# Peltier_activation_board.net
KiCad netlist of a schematic drawn in Altium Designer
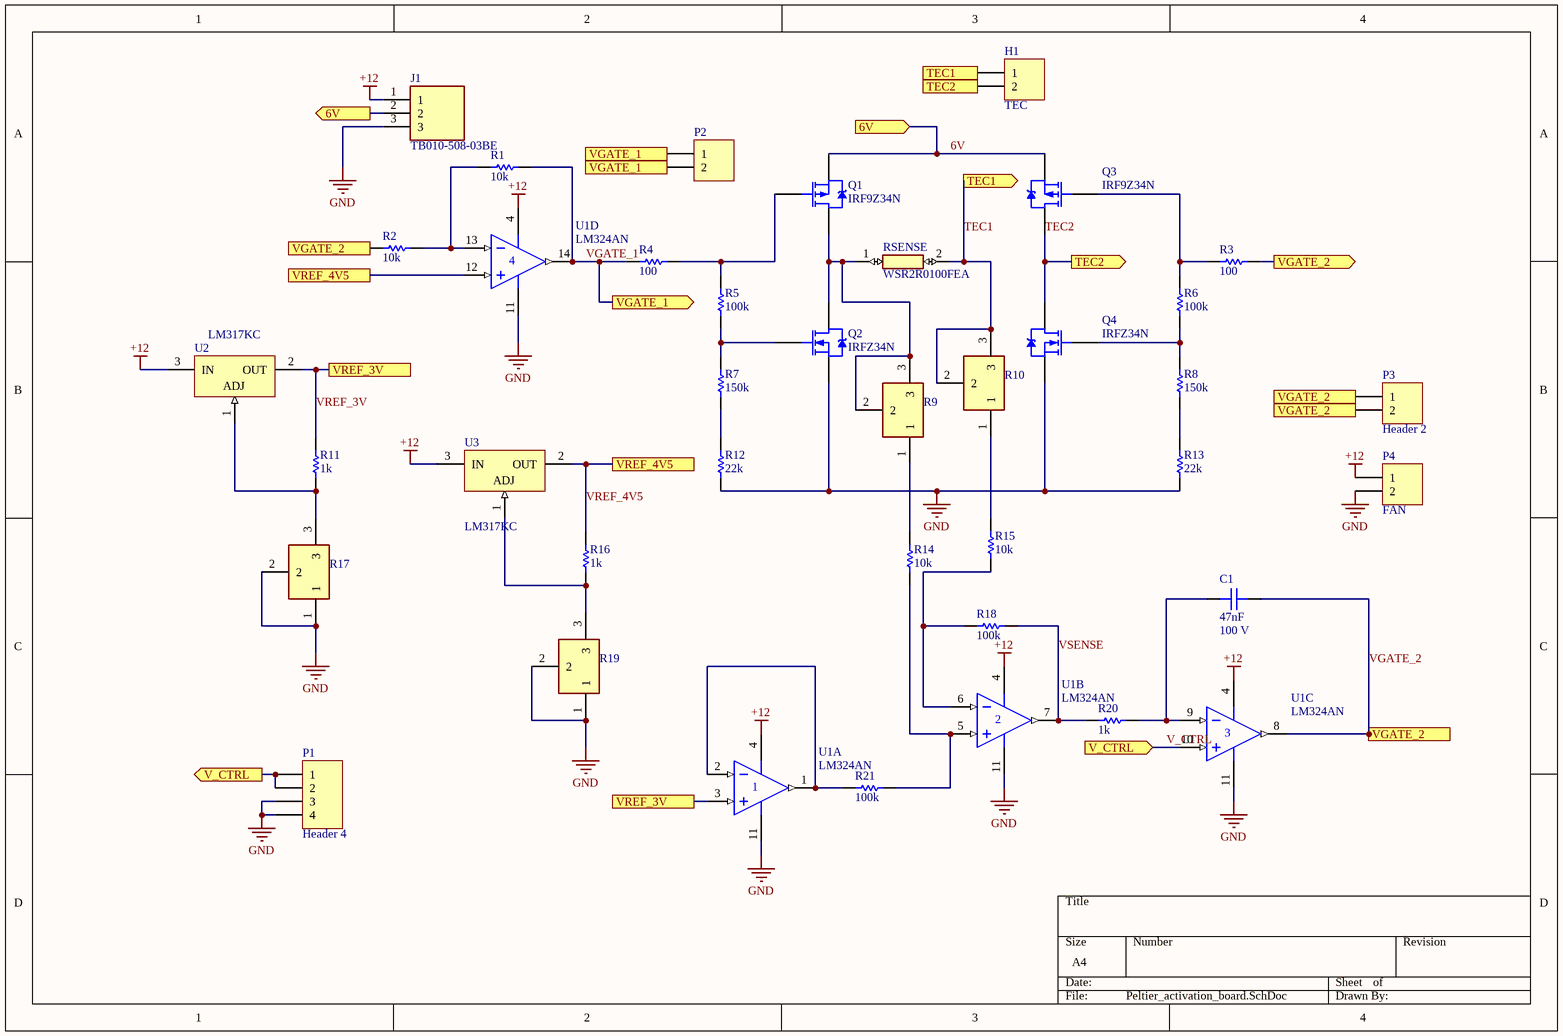
[diagram p0: Peltier_activation_board.SchDoc]

(export (version "E")
  (design (tool "Eeschema 10.0.6"))
  (components
    (comp (ref "C1")
      (value "47nF")
      (footprint "C100-200-100")
      (description "Capacitor")
      (fields (field (name "VOLTAGE") "100 V") (field (name "PUBLISHER") "Altium Limited"))
      (libsource (lib "Amplificador") (part "Capacitor"))
    )
    (comp (ref "H1")
      (value "TEC")
      (footprint "TB02")
      (description "Bloco terminal 1x2")
      (libsource (lib "Amplificador") (part "Terminal_1x2"))
    )
    (comp (ref "J1")
      (value "TB010-508-03BE")
      (footprint "SamacSys:TB01050803BE")
      (description "Connector")
      (fields (field (name "MOUSER PART NUMBER") "490-TB010-508-03BE"))
      (libsource (lib "*") (part "TB010-508-03BE"))
    )
    (comp (ref "P1")
      (value "Header 4")
      (footprint "HDR1X4")
      (description "Header, 4-Pin")
      (fields (field (name "PUBLISHER") "Altium Limited"))
      (libsource (lib "Miscellaneous Connectors") (part "Header 4"))
    )
    (comp (ref "P2")
      (value "~")
      (footprint "HDR1X2")
      (description "Header, 2-Pin")
      (fields (field (name "PUBLISHER") "Altium Limited"))
      (libsource (lib "Miscellaneous Connectors") (part "Header 2"))
    )
    (comp (ref "P3")
      (value "Header 2")
      (footprint "HDR1X2")
      (description "Header, 2-Pin")
      (fields (field (name "PUBLISHER") "Altium Limited"))
      (libsource (lib "Miscellaneous Connectors") (part "Header 2"))
    )
    (comp (ref "P4")
      (value "FAN")
      (footprint "HDR1X2")
      (description "Header, 2-Pin")
      (fields (field (name "PUBLISHER") "Altium Limited"))
      (libsource (lib "Miscellaneous Connectors") (part "Header 2"))
    )
    (comp (ref "Q1")
      (value "IRF9Z34N")
      (footprint "TO-220AB")
      (description "HEXFET Power MOSFET")
      (fields (field (name "PUBLISHER") "Altium Limited"))
      (libsource (lib "IR Discrete MOSFET - Power") (part "IRF9Z34N"))
    )
    (comp (ref "Q2")
      (value "IRFZ34N")
      (footprint "TO-220AB")
      (description "HEXFET Power MOSFET")
      (fields (field (name "PUBLISHER") "Altium Limited"))
      (libsource (lib "IR Discrete MOSFET - Power") (part "IRFZ34N"))
    )
    (comp (ref "Q3")
      (value "IRF9Z34N")
      (footprint "TO-220AB")
      (description "HEXFET Power MOSFET")
      (fields (field (name "PUBLISHER") "Altium Limited"))
      (libsource (lib "IR Discrete MOSFET - Power") (part "IRF9Z34N"))
    )
    (comp (ref "Q4")
      (value "IRFZ34N")
      (footprint "TO-220AB")
      (description "HEXFET Power MOSFET")
      (fields (field (name "PUBLISHER") "Altium Limited"))
      (libsource (lib "IR Discrete MOSFET - Power") (part "IRFZ34N"))
    )
    (comp (ref "R1")
      (value "10k")
      (footprint "R400-2.0mm")
      (description "Resistor")
      (fields
        (field (name "POWER") "1/8 W")
        (field (name "TOLERANCE") "5%")
        (field (name "PUBLISHER") "Altium Limited")
      )
      (libsource (lib "Amplificador") (part "Resistor"))
    )
    (comp (ref "R2")
      (value "10k")
      (footprint "R400-2.0mm")
      (description "Resistor")
      (fields
        (field (name "POWER") "1/8 W")
        (field (name "TOLERANCE") "5%")
        (field (name "PUBLISHER") "Altium Limited")
      )
      (libsource (lib "Amplificador") (part "Resistor"))
    )
    (comp (ref "R3")
      (value "100")
      (footprint "R400-2.0mm")
      (description "Resistor")
      (fields
        (field (name "POWER") "1/8 W")
        (field (name "TOLERANCE") "5%")
        (field (name "PUBLISHER") "Altium Limited")
      )
      (libsource (lib "Amplificador") (part "Resistor"))
    )
    (comp (ref "R4")
      (value "100")
      (footprint "R400-2.0mm")
      (description "Resistor")
      (fields
        (field (name "POWER") "1/8 W")
        (field (name "TOLERANCE") "5%")
        (field (name "PUBLISHER") "Altium Limited")
      )
      (libsource (lib "Amplificador") (part "Resistor"))
    )
    (comp (ref "R5")
      (value "100k")
      (footprint "R400-2.0mm")
      (description "Resistor")
      (fields
        (field (name "POWER") "1/8 W")
        (field (name "TOLERANCE") "5%")
        (field (name "PUBLISHER") "Altium Limited")
      )
      (libsource (lib "Amplificador") (part "Resistor"))
    )
    (comp (ref "R6")
      (value "100k")
      (footprint "R400-2.0mm")
      (description "Resistor")
      (fields
        (field (name "POWER") "1/8 W")
        (field (name "TOLERANCE") "5%")
        (field (name "PUBLISHER") "Altium Limited")
      )
      (libsource (lib "Amplificador") (part "Resistor"))
    )
    (comp (ref "R7")
      (value "150k")
      (footprint "R400-2.0mm")
      (description "Resistor")
      (fields
        (field (name "POWER") "1/8 W")
        (field (name "TOLERANCE") "5%")
        (field (name "PUBLISHER") "Altium Limited")
      )
      (libsource (lib "Amplificador") (part "Resistor"))
    )
    (comp (ref "R8")
      (value "150k")
      (footprint "R400-2.0mm")
      (description "Resistor")
      (fields
        (field (name "POWER") "1/8 W")
        (field (name "TOLERANCE") "5%")
        (field (name "PUBLISHER") "Altium Limited")
      )
      (libsource (lib "Amplificador") (part "Resistor"))
    )
    (comp (ref "R9")
      (value "3006P-1-103LF")
      (footprint "SamacSys:3006P_1")
      (description "Resistor")
      (fields (field (name "MOUSER PART NUMBER") "652-3006P-1-103-LF"))
      (libsource (lib "SamacSys") (part "3006P-1-103LF"))
    )
    (comp (ref "R10")
      (value "3006P-1-103LF")
      (footprint "SamacSys:3006P_1")
      (description "Resistor")
      (fields (field (name "MOUSER PART NUMBER") "652-3006P-1-103-LF"))
      (libsource (lib "SamacSys") (part "3006P-1-103LF"))
    )
    (comp (ref "R11")
      (value "1k")
      (footprint "R400-2.0mm")
      (description "Resistor")
      (fields
        (field (name "POWER") "1/8 W")
        (field (name "TOLERANCE") "5%")
        (field (name "PUBLISHER") "Altium Limited")
      )
      (libsource (lib "Amplificador") (part "Resistor"))
    )
    (comp (ref "R12")
      (value "22k")
      (footprint "R400-2.0mm")
      (description "Resistor")
      (fields
        (field (name "POWER") "1/8 W")
        (field (name "TOLERANCE") "5%")
        (field (name "PUBLISHER") "Altium Limited")
      )
      (libsource (lib "Amplificador") (part "Resistor"))
    )
    (comp (ref "R13")
      (value "22k")
      (footprint "R400-2.0mm")
      (description "Resistor")
      (fields
        (field (name "POWER") "1/8 W")
        (field (name "TOLERANCE") "5%")
        (field (name "PUBLISHER") "Altium Limited")
      )
      (libsource (lib "Amplificador") (part "Resistor"))
    )
    (comp (ref "R14")
      (value "10k")
      (footprint "R400-2.0mm")
      (description "Resistor")
      (fields
        (field (name "POWER") "1/8 W")
        (field (name "TOLERANCE") "5%")
        (field (name "PUBLISHER") "Altium Limited")
      )
      (libsource (lib "Amplificador") (part "Resistor"))
    )
    (comp (ref "R15")
      (value "10k")
      (footprint "R400-2.0mm")
      (description "Resistor")
      (fields
        (field (name "POWER") "1/8 W")
        (field (name "TOLERANCE") "5%")
        (field (name "PUBLISHER") "Altium Limited")
      )
      (libsource (lib "Amplificador") (part "Resistor"))
    )
    (comp (ref "R16")
      (value "1k")
      (footprint "R400-2.0mm")
      (description "Resistor")
      (fields
        (field (name "POWER") "1/8 W")
        (field (name "TOLERANCE") "5%")
        (field (name "PUBLISHER") "Altium Limited")
      )
      (libsource (lib "Amplificador") (part "Resistor"))
    )
    (comp (ref "R17")
      (value "3006P-1-103LF")
      (footprint "SamacSys:3006P_1")
      (description "Resistor")
      (fields (field (name "MOUSER PART NUMBER") "652-3006P-1-103-LF"))
      (libsource (lib "SamacSys") (part "3006P-1-103LF"))
    )
    (comp (ref "R18")
      (value "100k")
      (footprint "R400-2.0mm")
      (description "Resistor")
      (fields
        (field (name "POWER") "1/8 W")
        (field (name "TOLERANCE") "5%")
        (field (name "PUBLISHER") "Altium Limited")
      )
      (libsource (lib "Amplificador") (part "Resistor"))
    )
    (comp (ref "R19")
      (value "3006P-1-103LF")
      (footprint "SamacSys:3006P_1")
      (description "Resistor")
      (fields (field (name "MOUSER PART NUMBER") "652-3006P-1-103-LF"))
      (libsource (lib "SamacSys") (part "3006P-1-103LF"))
    )
    (comp (ref "R20")
      (value "1k")
      (footprint "R400-2.0mm")
      (description "Resistor")
      (fields
        (field (name "POWER") "1/8 W")
        (field (name "TOLERANCE") "5%")
        (field (name "PUBLISHER") "Altium Limited")
      )
      (libsource (lib "Amplificador") (part "Resistor"))
    )
    (comp (ref "R21")
      (value "100k")
      (footprint "R400-2.0mm")
      (description "Resistor")
      (fields
        (field (name "POWER") "1/8 W")
        (field (name "TOLERANCE") "5%")
        (field (name "PUBLISHER") "Altium Limited")
      )
      (libsource (lib "Amplificador") (part "Resistor"))
    )
    (comp (ref "RSENSE")
      (value "WSR2R0100FEA")
      (footprint "SamacSys:RESM11670X254N")
      (description "Resistor")
      (fields (field (name "MOUSER PART NUMBER") "71-WSR2R0100FEA"))
      (libsource (lib "*") (part "WSR2R0100FEA"))
    )
    (comp (ref "U1")
      (value "LM324AN")
      (footprint "N014")
      (description "Quadruple Operational Amplifier")
      (fields (field (name "PUBLISHER") "Altium Limited"))
      (libsource (lib "TI Operational Amplifier") (part "LM324AN"))
    )
    (comp (ref "U2")
      (value "LM317KC")
      (footprint "KC03")
      (description "3-Terminal Adjustable Regulator")
      (fields (field (name "PUBLISHER") "Altium Limited"))
      (libsource (lib "TI Power Mgt Voltage Regulator") (part "LM317KC"))
    )
    (comp (ref "U3")
      (value "LM317KC")
      (footprint "KC03")
      (description "3-Terminal Adjustable Regulator")
      (fields (field (name "PUBLISHER") "Altium Limited"))
      (libsource (lib "TI Power Mgt Voltage Regulator") (part "LM317KC"))
    )
  )
  (nets
    (net (code "1") (name "+12") (class "Default")
      (node (ref "J1") (pin "1") (pinfunction "1_1") (pintype "passive"))
      (node (ref "P4") (pin "1") (pinfunction "1_1") (pintype "passive"))
      (node (ref "U1") (pin "4") (pinfunction "V+_4") (pintype "power_in"))
      (node (ref "U2") (pin "3") (pinfunction "IN_3") (pintype "power_in"))
      (node (ref "U3") (pin "3") (pinfunction "IN_3") (pintype "power_in"))
    )
    (net (code "2") (name "/6V") (class "Default")
      (node (ref "J1") (pin "2") (pinfunction "2_2") (pintype "passive"))
      (node (ref "Q1") (pin "3") (pinfunction "S_3") (pintype "passive"))
      (node (ref "Q3") (pin "3") (pinfunction "S_3") (pintype "passive"))
    )
    (net (code "3") (name "/TEC1") (class "Default")
      (node (ref "H1") (pin "1") (pinfunction "1_1") (pintype "passive"))
      (node (ref "R10") (pin "2") (pinfunction "2_2") (pintype "passive"))
      (node (ref "R10") (pin "3") (pinfunction "3_3") (pintype "passive"))
      (node (ref "RSENSE") (pin "2") (pinfunction "2_2") (pintype "bidirectional"))
    )
    (net (code "4") (name "/TEC2") (class "Default")
      (node (ref "H1") (pin "2") (pinfunction "2_2") (pintype "passive"))
      (node (ref "Q3") (pin "2") (pinfunction "D_2") (pintype "passive"))
      (node (ref "Q4") (pin "2") (pinfunction "D_2") (pintype "passive"))
    )
    (net (code "5") (name "/VGATE_1") (class "Default")
      (node (ref "P2") (pin "1") (pinfunction "1_1") (pintype "passive"))
      (node (ref "P2") (pin "2") (pinfunction "2_2") (pintype "passive"))
      (node (ref "R1") (pin "1") (pinfunction "1_1") (pintype "passive"))
      (node (ref "R4") (pin "2") (pinfunction "2_2") (pintype "passive"))
      (node (ref "U1") (pin "14") (pinfunction "OUT_14") (pintype "output"))
    )
    (net (code "6") (name "/VGATE_2") (class "Default")
      (node (ref "C1") (pin "2") (pinfunction "2_2") (pintype "passive"))
      (node (ref "P3") (pin "1") (pinfunction "1_1") (pintype "passive"))
      (node (ref "P3") (pin "2") (pinfunction "2_2") (pintype "passive"))
      (node (ref "R2") (pin "2") (pinfunction "2_2") (pintype "passive"))
      (node (ref "R3") (pin "1") (pinfunction "1_1") (pintype "passive"))
      (node (ref "U1") (pin "8") (pinfunction "OUT_8") (pintype "output"))
    )
    (net (code "7") (name "/VREF_3V") (class "Default")
      (node (ref "R11") (pin "2") (pinfunction "2_2") (pintype "passive"))
      (node (ref "U1") (pin "3") (pinfunction "IN+_3") (pintype "input"))
      (node (ref "U2") (pin "2") (pinfunction "OUT_2") (pintype "power_in"))
    )
    (net (code "8") (name "/VREF_4V5") (class "Default")
      (node (ref "R16") (pin "2") (pinfunction "2_2") (pintype "passive"))
      (node (ref "U1") (pin "12") (pinfunction "IN+_12") (pintype "input"))
      (node (ref "U3") (pin "2") (pinfunction "OUT_2") (pintype "power_in"))
    )
    (net (code "9") (name "/VSENSE") (class "Default")
      (node (ref "R18") (pin "2") (pinfunction "2_2") (pintype "passive"))
      (node (ref "R20") (pin "1") (pinfunction "1_1") (pintype "passive"))
      (node (ref "U1") (pin "7") (pinfunction "OUT_7") (pintype "output"))
    )
    (net (code "10") (name "/V_CTRL") (class "Default")
      (node (ref "P1") (pin "1") (pinfunction "1_1") (pintype "passive"))
      (node (ref "P1") (pin "2") (pinfunction "2_2") (pintype "passive"))
      (node (ref "U1") (pin "10") (pinfunction "IN+_10") (pintype "input"))
    )
    (net (code "11") (name "GND") (class "Default")
      (node (ref "J1") (pin "3") (pinfunction "3_3") (pintype "passive"))
      (node (ref "P1") (pin "3") (pinfunction "3_3") (pintype "passive"))
      (node (ref "P1") (pin "4") (pinfunction "4_4") (pintype "passive"))
      (node (ref "P4") (pin "2") (pinfunction "2_2") (pintype "passive"))
      (node (ref "Q2") (pin "3") (pinfunction "S_3") (pintype "passive"))
      (node (ref "Q4") (pin "3") (pinfunction "S_3") (pintype "passive"))
      (node (ref "R12") (pin "2") (pinfunction "2_2") (pintype "passive"))
      (node (ref "R13") (pin "2") (pinfunction "2_2") (pintype "passive"))
      (node (ref "R17") (pin "1") (pinfunction "1_1") (pintype "passive"))
      (node (ref "R17") (pin "2") (pinfunction "2_2") (pintype "passive"))
      (node (ref "R19") (pin "1") (pinfunction "1_1") (pintype "passive"))
      (node (ref "R19") (pin "2") (pinfunction "2_2") (pintype "passive"))
      (node (ref "U1") (pin "11") (pinfunction "V-_11") (pintype "power_in"))
    )
    (net (code "12") (name "Net-(Q1-D)") (class "Default")
      (node (ref "Q1") (pin "2") (pinfunction "D_2") (pintype "passive"))
      (node (ref "Q2") (pin "2") (pinfunction "D_2") (pintype "passive"))
      (node (ref "R9") (pin "2") (pinfunction "2_2") (pintype "passive"))
      (node (ref "R9") (pin "3") (pinfunction "3_3") (pintype "passive"))
      (node (ref "RSENSE") (pin "1") (pinfunction "1_1") (pintype "bidirectional"))
    )
    (net (code "13") (name "Net-(Q1-G)") (class "Default")
      (node (ref "Q1") (pin "1") (pinfunction "G_1") (pintype "passive"))
      (node (ref "R4") (pin "1") (pinfunction "1_1") (pintype "passive"))
      (node (ref "R5") (pin "1") (pinfunction "1_1") (pintype "passive"))
    )
    (net (code "14") (name "Net-(Q2-G)") (class "Default")
      (node (ref "Q2") (pin "1") (pinfunction "G_1") (pintype "passive"))
      (node (ref "R5") (pin "2") (pinfunction "2_2") (pintype "passive"))
      (node (ref "R7") (pin "1") (pinfunction "1_1") (pintype "passive"))
    )
    (net (code "15") (name "Net-(Q3-G)") (class "Default")
      (node (ref "Q3") (pin "1") (pinfunction "G_1") (pintype "passive"))
      (node (ref "R3") (pin "2") (pinfunction "2_2") (pintype "passive"))
      (node (ref "R6") (pin "1") (pinfunction "1_1") (pintype "passive"))
    )
    (net (code "16") (name "Net-(Q4-G)") (class "Default")
      (node (ref "Q4") (pin "1") (pinfunction "G_1") (pintype "passive"))
      (node (ref "R6") (pin "2") (pinfunction "2_2") (pintype "passive"))
      (node (ref "R8") (pin "1") (pinfunction "1_1") (pintype "passive"))
    )
    (net (code "17") (name "Net-(R10-Pad1)") (class "Default")
      (node (ref "R10") (pin "1") (pinfunction "1_1") (pintype "passive"))
      (node (ref "R15") (pin "2") (pinfunction "2_2") (pintype "passive"))
    )
    (net (code "18") (name "Net-(R12-Pad1)") (class "Default")
      (node (ref "R12") (pin "1") (pinfunction "1_1") (pintype "passive"))
      (node (ref "R7") (pin "2") (pinfunction "2_2") (pintype "passive"))
    )
    (net (code "19") (name "Net-(R13-Pad1)") (class "Default")
      (node (ref "R13") (pin "1") (pinfunction "1_1") (pintype "passive"))
      (node (ref "R8") (pin "2") (pinfunction "2_2") (pintype "passive"))
    )
    (net (code "20") (name "Net-(R14-Pad2)") (class "Default")
      (node (ref "R14") (pin "2") (pinfunction "2_2") (pintype "passive"))
      (node (ref "R9") (pin "1") (pinfunction "1_1") (pintype "passive"))
    )
    (net (code "21") (name "Net-(U1A-IN-)") (class "Default")
      (node (ref "R21") (pin "1") (pinfunction "1_1") (pintype "passive"))
      (node (ref "U1") (pin "1") (pinfunction "OUT_1") (pintype "output"))
      (node (ref "U1") (pin "2") (pinfunction "IN-_2") (pintype "input"))
    )
    (net (code "22") (name "Net-(U1B-IN+)") (class "Default")
      (node (ref "R14") (pin "1") (pinfunction "1_1") (pintype "passive"))
      (node (ref "R21") (pin "2") (pinfunction "2_2") (pintype "passive"))
      (node (ref "U1") (pin "5") (pinfunction "IN+_5") (pintype "input"))
    )
    (net (code "23") (name "Net-(U1B-IN-)") (class "Default")
      (node (ref "R15") (pin "1") (pinfunction "1_1") (pintype "passive"))
      (node (ref "R18") (pin "1") (pinfunction "1_1") (pintype "passive"))
      (node (ref "U1") (pin "6") (pinfunction "IN-_6") (pintype "input"))
    )
    (net (code "24") (name "Net-(U1C-IN-)") (class "Default")
      (node (ref "C1") (pin "1") (pinfunction "1_1") (pintype "passive"))
      (node (ref "R20") (pin "2") (pinfunction "2_2") (pintype "passive"))
      (node (ref "U1") (pin "9") (pinfunction "IN-_9") (pintype "input"))
    )
    (net (code "25") (name "Net-(U1D-IN-)") (class "Default")
      (node (ref "R1") (pin "2") (pinfunction "2_2") (pintype "passive"))
      (node (ref "R2") (pin "1") (pinfunction "1_1") (pintype "passive"))
      (node (ref "U1") (pin "13") (pinfunction "IN-_13") (pintype "input"))
    )
    (net (code "26") (name "Net-(U2-ADJ)") (class "Default")
      (node (ref "R11") (pin "1") (pinfunction "1_1") (pintype "passive"))
      (node (ref "R17") (pin "3") (pinfunction "3_3") (pintype "passive"))
      (node (ref "U2") (pin "1") (pinfunction "ADJ_1") (pintype "input"))
    )
    (net (code "27") (name "Net-(U3-ADJ)") (class "Default")
      (node (ref "R16") (pin "1") (pinfunction "1_1") (pintype "passive"))
      (node (ref "R19") (pin "3") (pinfunction "3_3") (pintype "passive"))
      (node (ref "U3") (pin "1") (pinfunction "ADJ_1") (pintype "input"))
    )
  )
)
